# v0_1sch.net
KiCad netlist of a schematic drawn in EAGLE
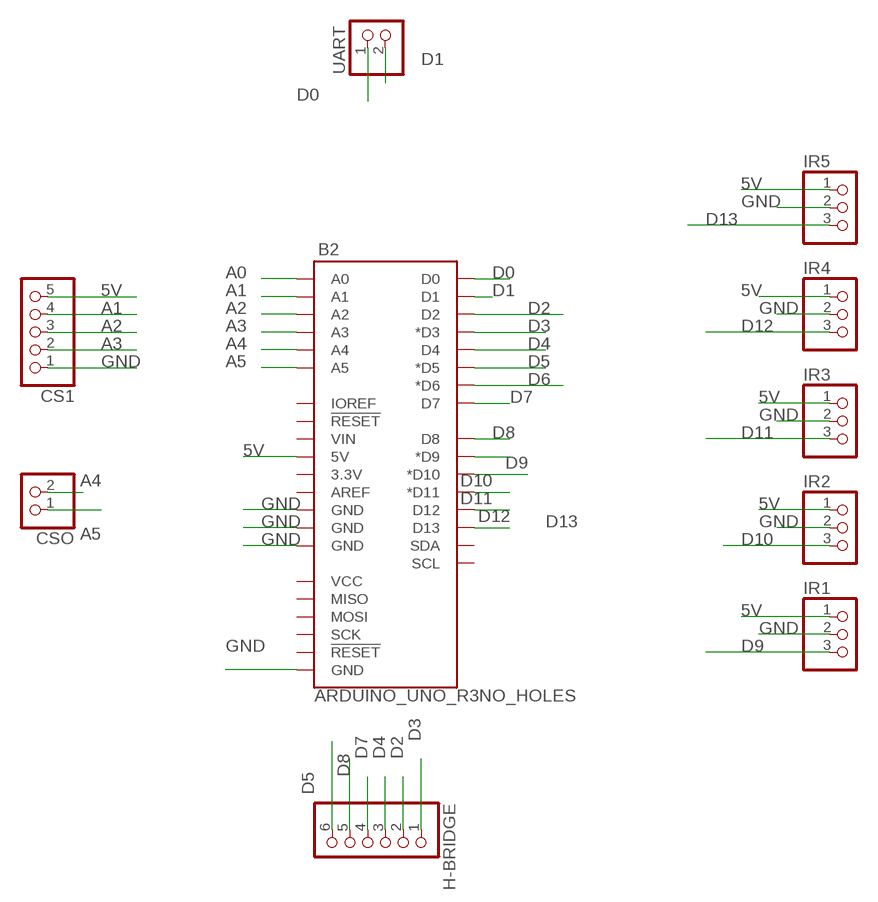
[diagram p0: schematic, sheet 1]

(export (version "E")
  (design (tool "Eeschema 10.0.6"))
  (components
    (comp (ref "B2")
      (value "ARDUINO_UNO_R3NO_HOLES")
      (footprint "eagle-import:ARDUINO_R3_NO_HOLES")
      (libsource (lib "eagle-import") (part "ARDUINO_UNO_R3NO_HOLES"))
    )
    (comp (ref "CS1")
      (value "PINHD-1X5")
      (footprint "eagle-import:1X05")
      (libsource (lib "eagle-import") (part "PINHD-1X5"))
    )
    (comp (ref "CSO")
      (value "PINHD-1X2")
      (footprint "eagle-import:1X02")
      (libsource (lib "eagle-import") (part "PINHD-1X2"))
    )
    (comp (ref "H-BRIDGE")
      (value "PINHD-1X6")
      (footprint "eagle-import:1X06")
      (libsource (lib "eagle-import") (part "PINHD-1X6"))
    )
    (comp (ref "IR1")
      (value "PINHD-1X3")
      (footprint "eagle-import:1X03")
      (libsource (lib "eagle-import") (part "PINHD-1X3"))
    )
    (comp (ref "IR2")
      (value "PINHD-1X3")
      (footprint "eagle-import:1X03")
      (libsource (lib "eagle-import") (part "PINHD-1X3"))
    )
    (comp (ref "IR3")
      (value "PINHD-1X3")
      (footprint "eagle-import:1X03")
      (libsource (lib "eagle-import") (part "PINHD-1X3"))
    )
    (comp (ref "IR4")
      (value "PINHD-1X3")
      (footprint "eagle-import:1X03")
      (libsource (lib "eagle-import") (part "PINHD-1X3"))
    )
    (comp (ref "IR5")
      (value "PINHD-1X3")
      (footprint "eagle-import:1X03")
      (libsource (lib "eagle-import") (part "PINHD-1X3"))
    )
    (comp (ref "UART")
      (value "PINHD-1X2")
      (footprint "eagle-import:1X02")
      (libsource (lib "eagle-import") (part "PINHD-1X2"))
    )
  )
  (nets
    (net (code "1") (name "/5V") (class "Default")
      (node (ref "B2") (pin "5V") (pinfunction "5V_5V") (pintype "bidirectional"))
      (node (ref "CS1") (pin "5") (pinfunction "5_5") (pintype "passive"))
      (node (ref "IR1") (pin "1") (pinfunction "1_1") (pintype "passive"))
      (node (ref "IR2") (pin "1") (pinfunction "1_1") (pintype "passive"))
      (node (ref "IR3") (pin "1") (pinfunction "1_1") (pintype "passive"))
      (node (ref "IR4") (pin "1") (pinfunction "1_1") (pintype "passive"))
      (node (ref "IR5") (pin "1") (pinfunction "1_1") (pintype "passive"))
    )
    (net (code "2") (name "/A0") (class "Default")
      (node (ref "B2") (pin "A0") (pinfunction "A0_A0") (pintype "bidirectional"))
    )
    (net (code "3") (name "/A1") (class "Default")
      (node (ref "B2") (pin "A1") (pinfunction "A1_A1") (pintype "bidirectional"))
      (node (ref "CS1") (pin "4") (pinfunction "4_4") (pintype "passive"))
    )
    (net (code "4") (name "/A2") (class "Default")
      (node (ref "B2") (pin "A2") (pinfunction "A2_A2") (pintype "bidirectional"))
      (node (ref "CS1") (pin "3") (pinfunction "3_3") (pintype "passive"))
    )
    (net (code "5") (name "/A3") (class "Default")
      (node (ref "B2") (pin "A3") (pinfunction "A3_A3") (pintype "bidirectional"))
      (node (ref "CS1") (pin "2") (pinfunction "2_2") (pintype "passive"))
    )
    (net (code "6") (name "/A4") (class "Default")
      (node (ref "B2") (pin "A4") (pinfunction "A4_A4") (pintype "bidirectional"))
      (node (ref "CSO") (pin "2") (pinfunction "2_2") (pintype "passive"))
    )
    (net (code "7") (name "/A5") (class "Default")
      (node (ref "B2") (pin "A5") (pinfunction "A5_A5") (pintype "bidirectional"))
      (node (ref "CSO") (pin "1") (pinfunction "1_1") (pintype "passive"))
    )
    (net (code "8") (name "/D0") (class "Default")
      (node (ref "B2") (pin "D0") (pinfunction "D0_D0") (pintype "bidirectional"))
      (node (ref "UART") (pin "1") (pinfunction "1_1") (pintype "passive"))
    )
    (net (code "9") (name "/D1") (class "Default")
      (node (ref "B2") (pin "D1") (pinfunction "D1_D1") (pintype "bidirectional"))
      (node (ref "UART") (pin "2") (pinfunction "2_2") (pintype "passive"))
    )
    (net (code "10") (name "/D2") (class "Default")
      (node (ref "B2") (pin "D2") (pinfunction "D2_D2") (pintype "bidirectional"))
      (node (ref "H-BRIDGE") (pin "2") (pinfunction "2_2") (pintype "passive"))
    )
    (net (code "11") (name "/D3") (class "Default")
      (node (ref "B2") (pin "D3") (pinfunction "*D3_D3") (pintype "bidirectional"))
      (node (ref "H-BRIDGE") (pin "1") (pinfunction "1_1") (pintype "passive"))
    )
    (net (code "12") (name "/D4") (class "Default")
      (node (ref "B2") (pin "D4") (pinfunction "D4_D4") (pintype "bidirectional"))
      (node (ref "H-BRIDGE") (pin "3") (pinfunction "3_3") (pintype "passive"))
    )
    (net (code "13") (name "/D5") (class "Default")
      (node (ref "B2") (pin "D5") (pinfunction "*D5_D5") (pintype "bidirectional"))
      (node (ref "H-BRIDGE") (pin "6") (pinfunction "6_6") (pintype "passive"))
    )
    (net (code "14") (name "/D6") (class "Default")
      (node (ref "B2") (pin "D6") (pinfunction "*D6_D6") (pintype "bidirectional"))
    )
    (net (code "15") (name "/D7") (class "Default")
      (node (ref "B2") (pin "D7") (pinfunction "D7_D7") (pintype "bidirectional"))
      (node (ref "H-BRIDGE") (pin "4") (pinfunction "4_4") (pintype "passive"))
    )
    (net (code "16") (name "/D8") (class "Default")
      (node (ref "B2") (pin "D8") (pinfunction "D8_D8") (pintype "bidirectional"))
      (node (ref "H-BRIDGE") (pin "5") (pinfunction "5_5") (pintype "passive"))
    )
    (net (code "17") (name "/D9") (class "Default")
      (node (ref "B2") (pin "D9") (pinfunction "*D9_D9") (pintype "bidirectional"))
      (node (ref "IR1") (pin "3") (pinfunction "3_3") (pintype "passive"))
    )
    (net (code "18") (name "/D10") (class "Default")
      (node (ref "B2") (pin "D10") (pinfunction "*D10_D10") (pintype "bidirectional"))
      (node (ref "IR2") (pin "3") (pinfunction "3_3") (pintype "passive"))
    )
    (net (code "19") (name "/D11") (class "Default")
      (node (ref "B2") (pin "D11") (pinfunction "*D11_D11") (pintype "bidirectional"))
      (node (ref "IR3") (pin "3") (pinfunction "3_3") (pintype "passive"))
    )
    (net (code "20") (name "/D12") (class "Default")
      (node (ref "B2") (pin "D12") (pinfunction "D12_D12") (pintype "bidirectional"))
      (node (ref "IR4") (pin "3") (pinfunction "3_3") (pintype "passive"))
    )
    (net (code "21") (name "/D13") (class "Default")
      (node (ref "B2") (pin "D13") (pinfunction "D13_D13") (pintype "bidirectional"))
      (node (ref "IR5") (pin "3") (pinfunction "3_3") (pintype "passive"))
    )
    (net (code "22") (name "/GND") (class "Default")
      (node (ref "B2") (pin "GND@1") (pinfunction "GND_GND@1") (pintype "bidirectional"))
      (node (ref "B2") (pin "GND@2") (pinfunction "GND_GND@2") (pintype "bidirectional"))
      (node (ref "B2") (pin "GND@3") (pinfunction "GND_GND@3") (pintype "bidirectional"))
      (node (ref "B2") (pin "GND@4") (pinfunction "GND_GND@4") (pintype "bidirectional"))
      (node (ref "CS1") (pin "1") (pinfunction "1_1") (pintype "passive"))
      (node (ref "IR1") (pin "2") (pinfunction "2_2") (pintype "passive"))
      (node (ref "IR2") (pin "2") (pinfunction "2_2") (pintype "passive"))
      (node (ref "IR3") (pin "2") (pinfunction "2_2") (pintype "passive"))
      (node (ref "IR4") (pin "2") (pinfunction "2_2") (pintype "passive"))
      (node (ref "IR5") (pin "2") (pinfunction "2_2") (pintype "passive"))
    )
    (net (code "23") (name "unconnected-(B2-Pad3.3V)") (class "Default")
      (node (ref "B2") (pin "3.3V") (pinfunction "3.3V_3.3V") (pintype "bidirectional"))
    )
    (net (code "24") (name "unconnected-(B2-PadAREF)") (class "Default")
      (node (ref "B2") (pin "AREF") (pinfunction "AREF_AREF") (pintype "bidirectional"))
    )
    (net (code "25") (name "unconnected-(B2-PadIOREF)") (class "Default")
      (node (ref "B2") (pin "IOREF") (pinfunction "IOREF_IOREF") (pintype "bidirectional"))
    )
    (net (code "26") (name "unconnected-(B2-PadMISO)") (class "Default")
      (node (ref "B2") (pin "MISO") (pinfunction "MISO_MISO") (pintype "bidirectional"))
    )
    (net (code "27") (name "unconnected-(B2-PadMOSI)") (class "Default")
      (node (ref "B2") (pin "MOSI") (pinfunction "MOSI_MOSI") (pintype "bidirectional"))
    )
    (net (code "28") (name "unconnected-(B2-PadSCK)") (class "Default")
      (node (ref "B2") (pin "SCK") (pinfunction "SCK_SCK") (pintype "bidirectional"))
    )
    (net (code "29") (name "unconnected-(B2-PadSCL)") (class "Default")
      (node (ref "B2") (pin "SCL") (pinfunction "SCL_SCL") (pintype "bidirectional"))
    )
    (net (code "30") (name "unconnected-(B2-PadSDA)") (class "Default")
      (node (ref "B2") (pin "SDA") (pinfunction "SDA_SDA") (pintype "bidirectional"))
    )
    (net (code "31") (name "unconnected-(B2-PadVCC)") (class "Default")
      (node (ref "B2") (pin "VCC") (pinfunction "VCC_VCC") (pintype "bidirectional"))
    )
    (net (code "32") (name "unconnected-(B2-PadVIN)") (class "Default")
      (node (ref "B2") (pin "VIN") (pinfunction "VIN_VIN") (pintype "bidirectional"))
    )
    (net (code "33") (name "unconnected-(B2-~{RESET}-PadRESET@1)") (class "Default")
      (node (ref "B2") (pin "RESET@1") (pinfunction "~{RESET}_RESET@1") (pintype "bidirectional"))
    )
    (net (code "34") (name "unconnected-(B2-~{RESET}-PadRESET@2)") (class "Default")
      (node (ref "B2") (pin "RESET@2") (pinfunction "~{RESET}_RESET@2") (pintype "bidirectional"))
    )
  )
)
